# IoT_Sight.net
KiCad netlist of a schematic drawn in EAGLE
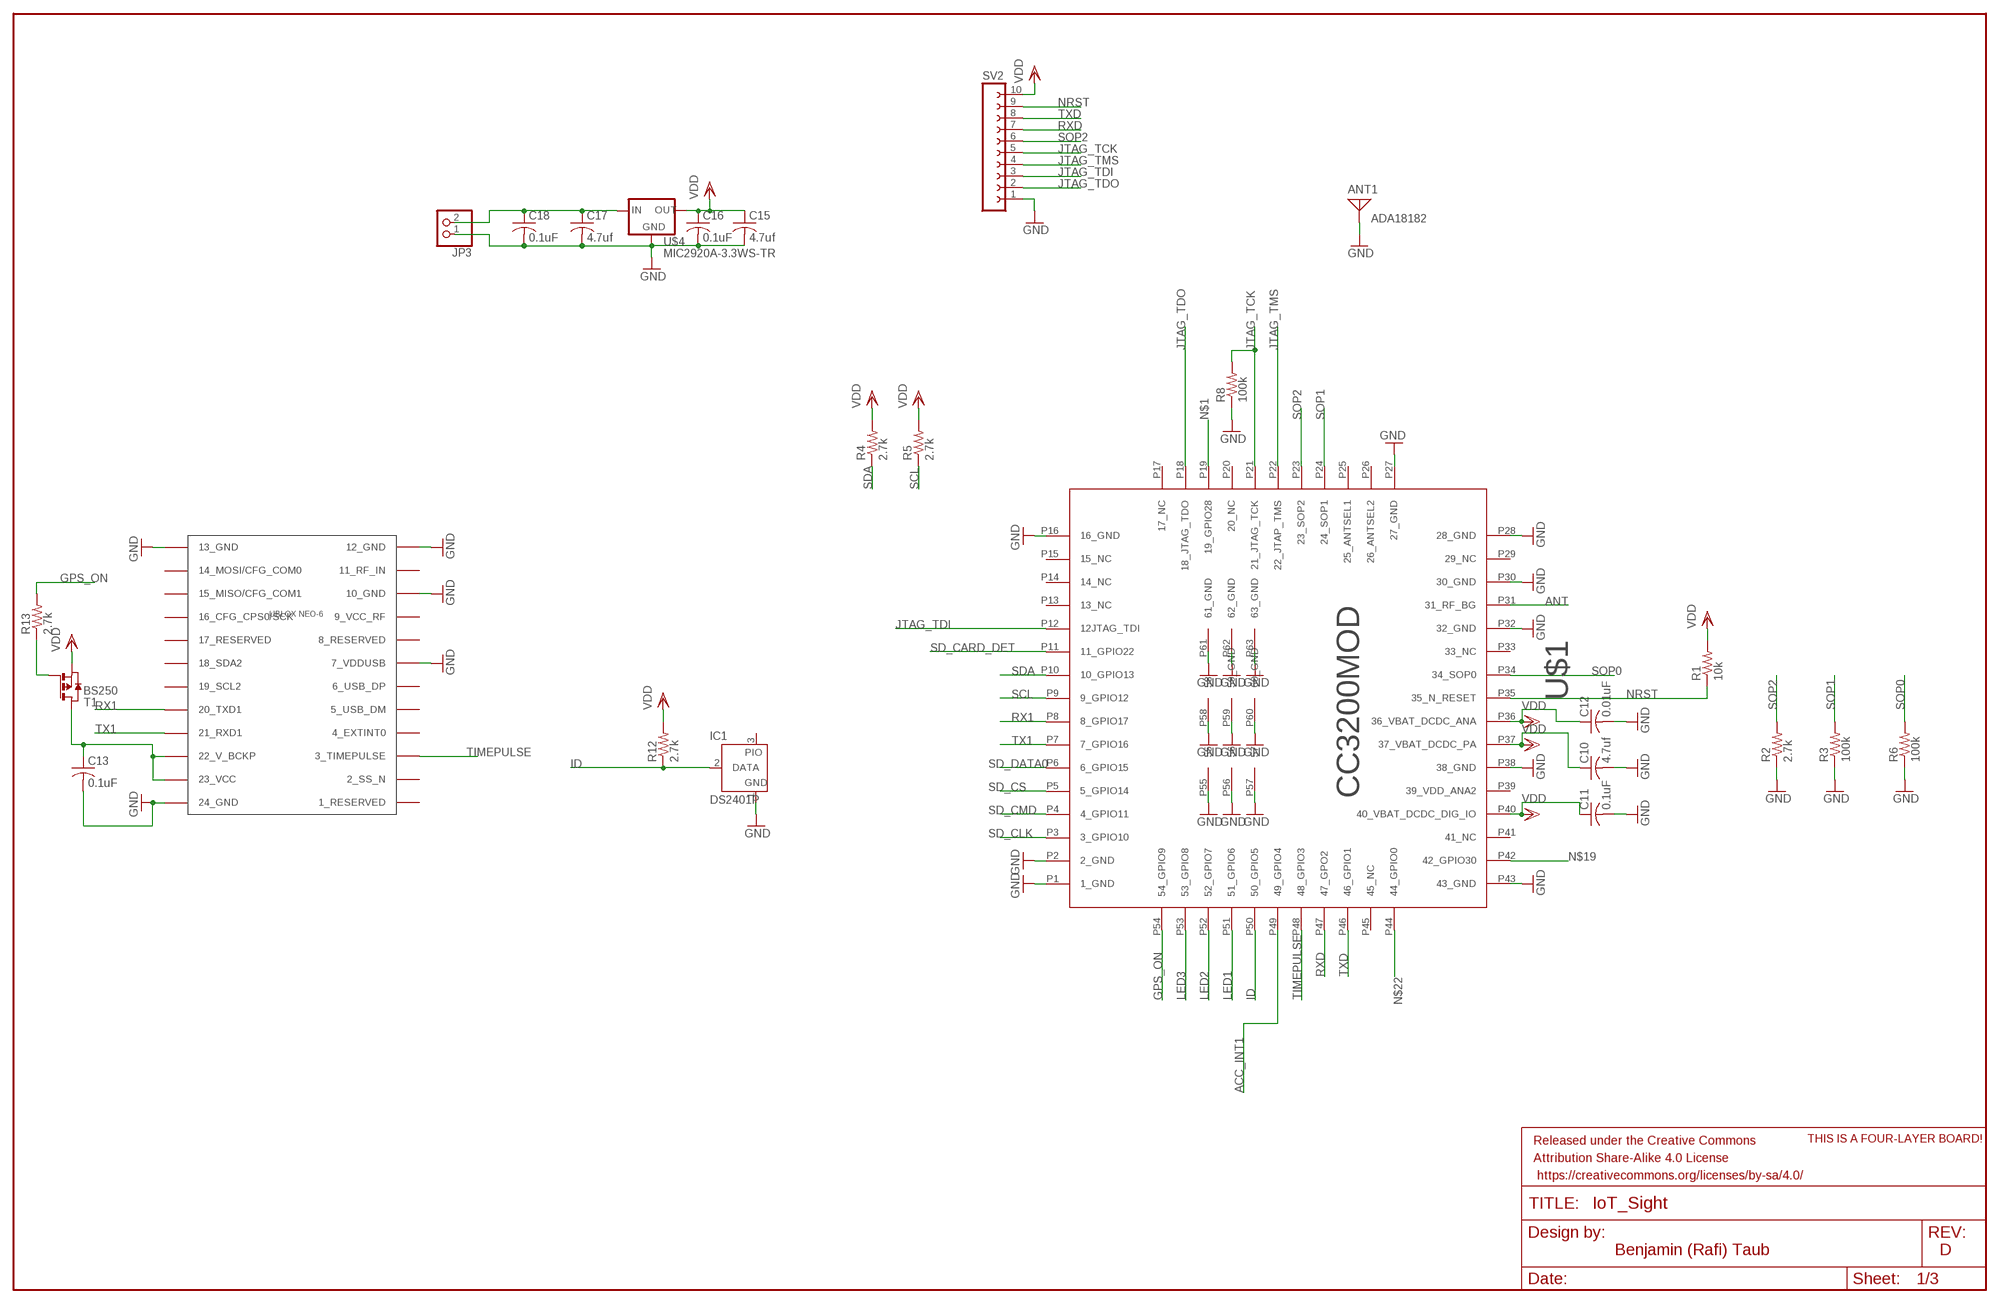
[diagram p0: schematic, sheet 1]
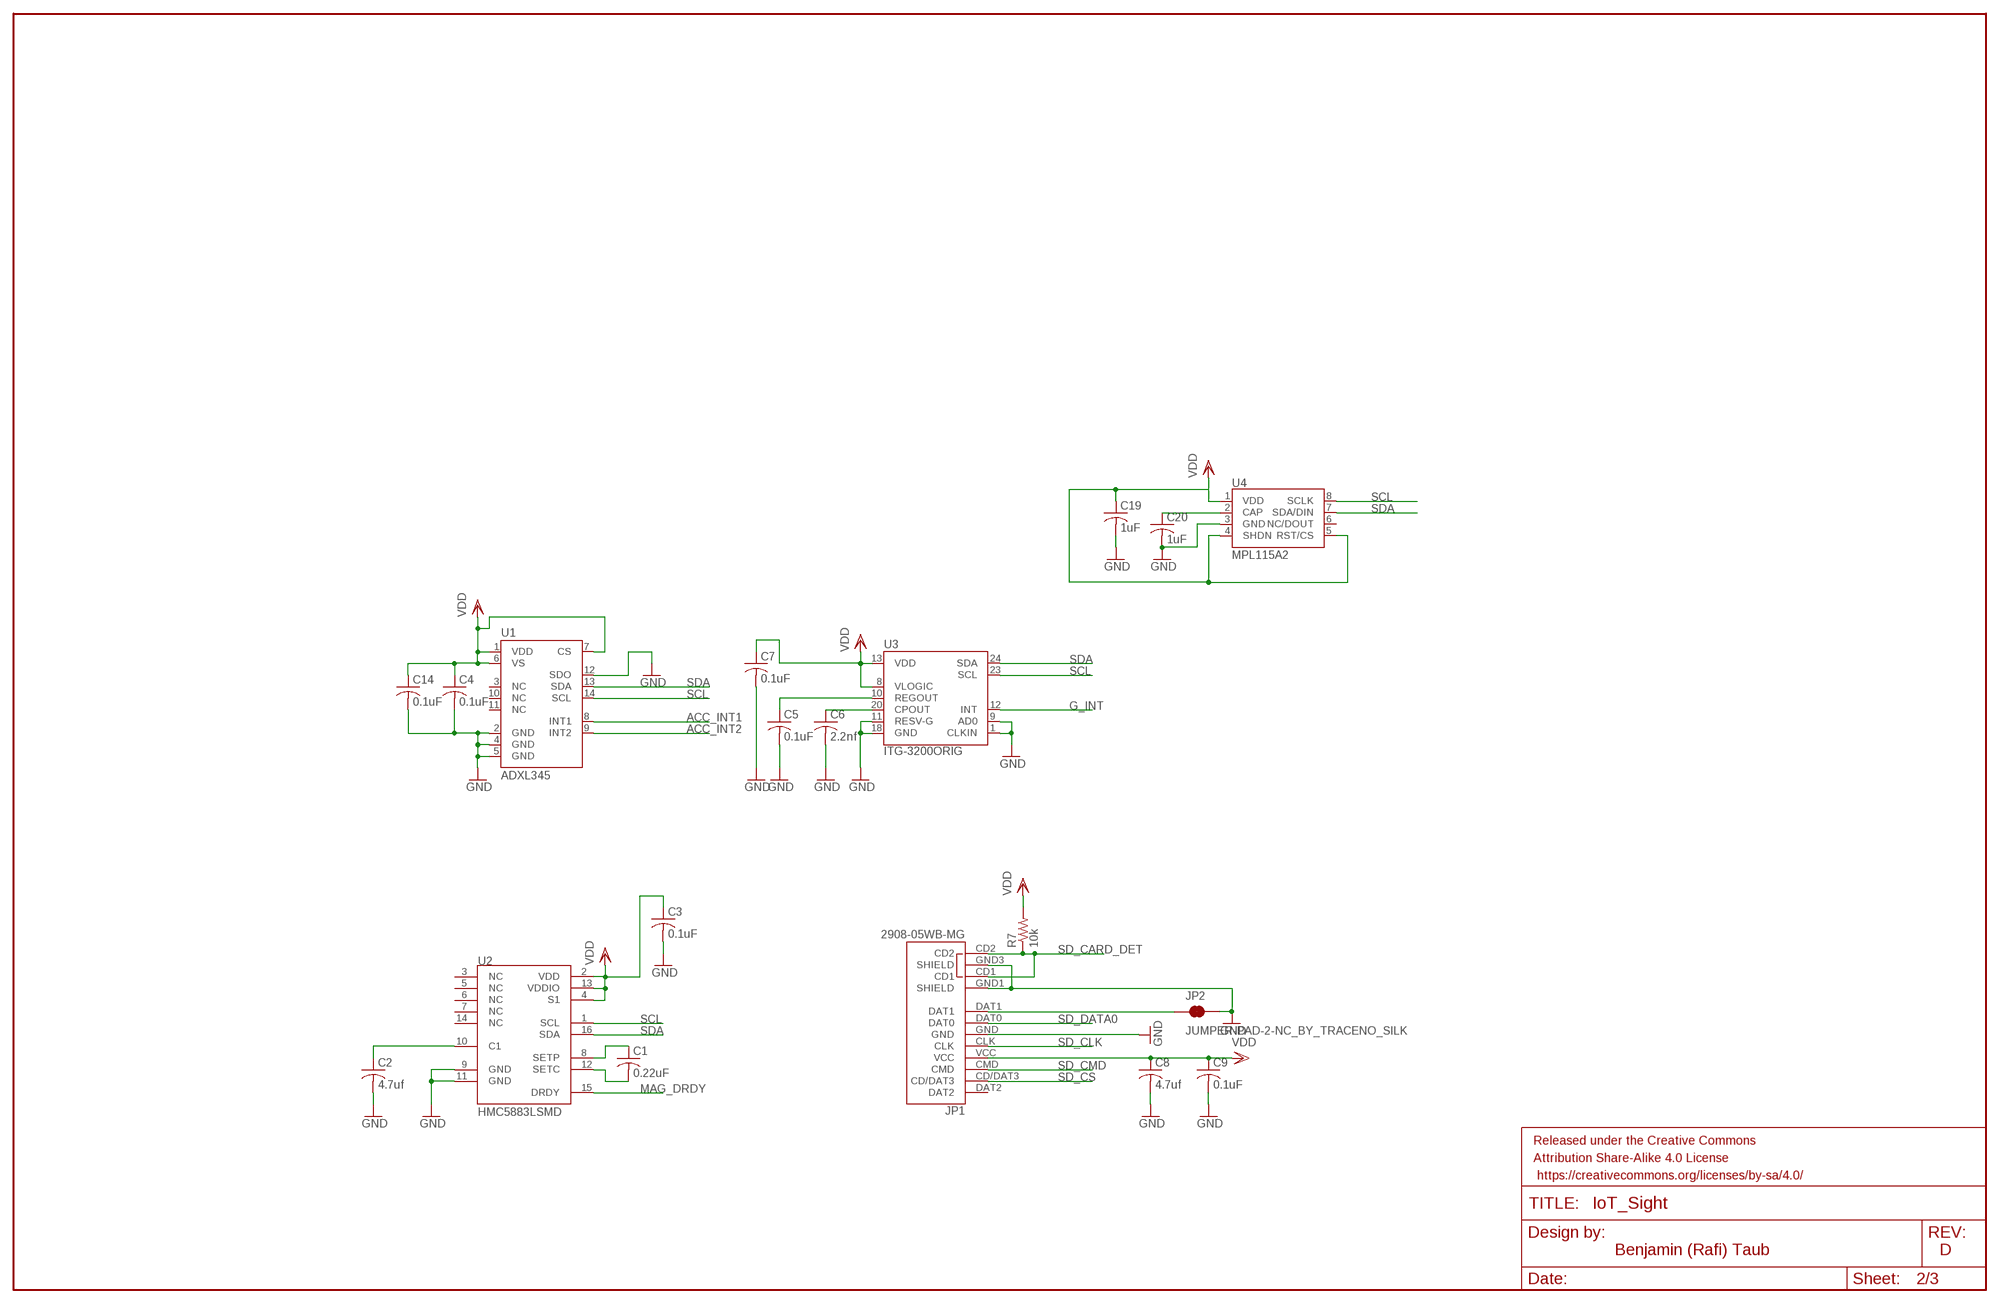
[diagram p1: schematic, sheet 2]
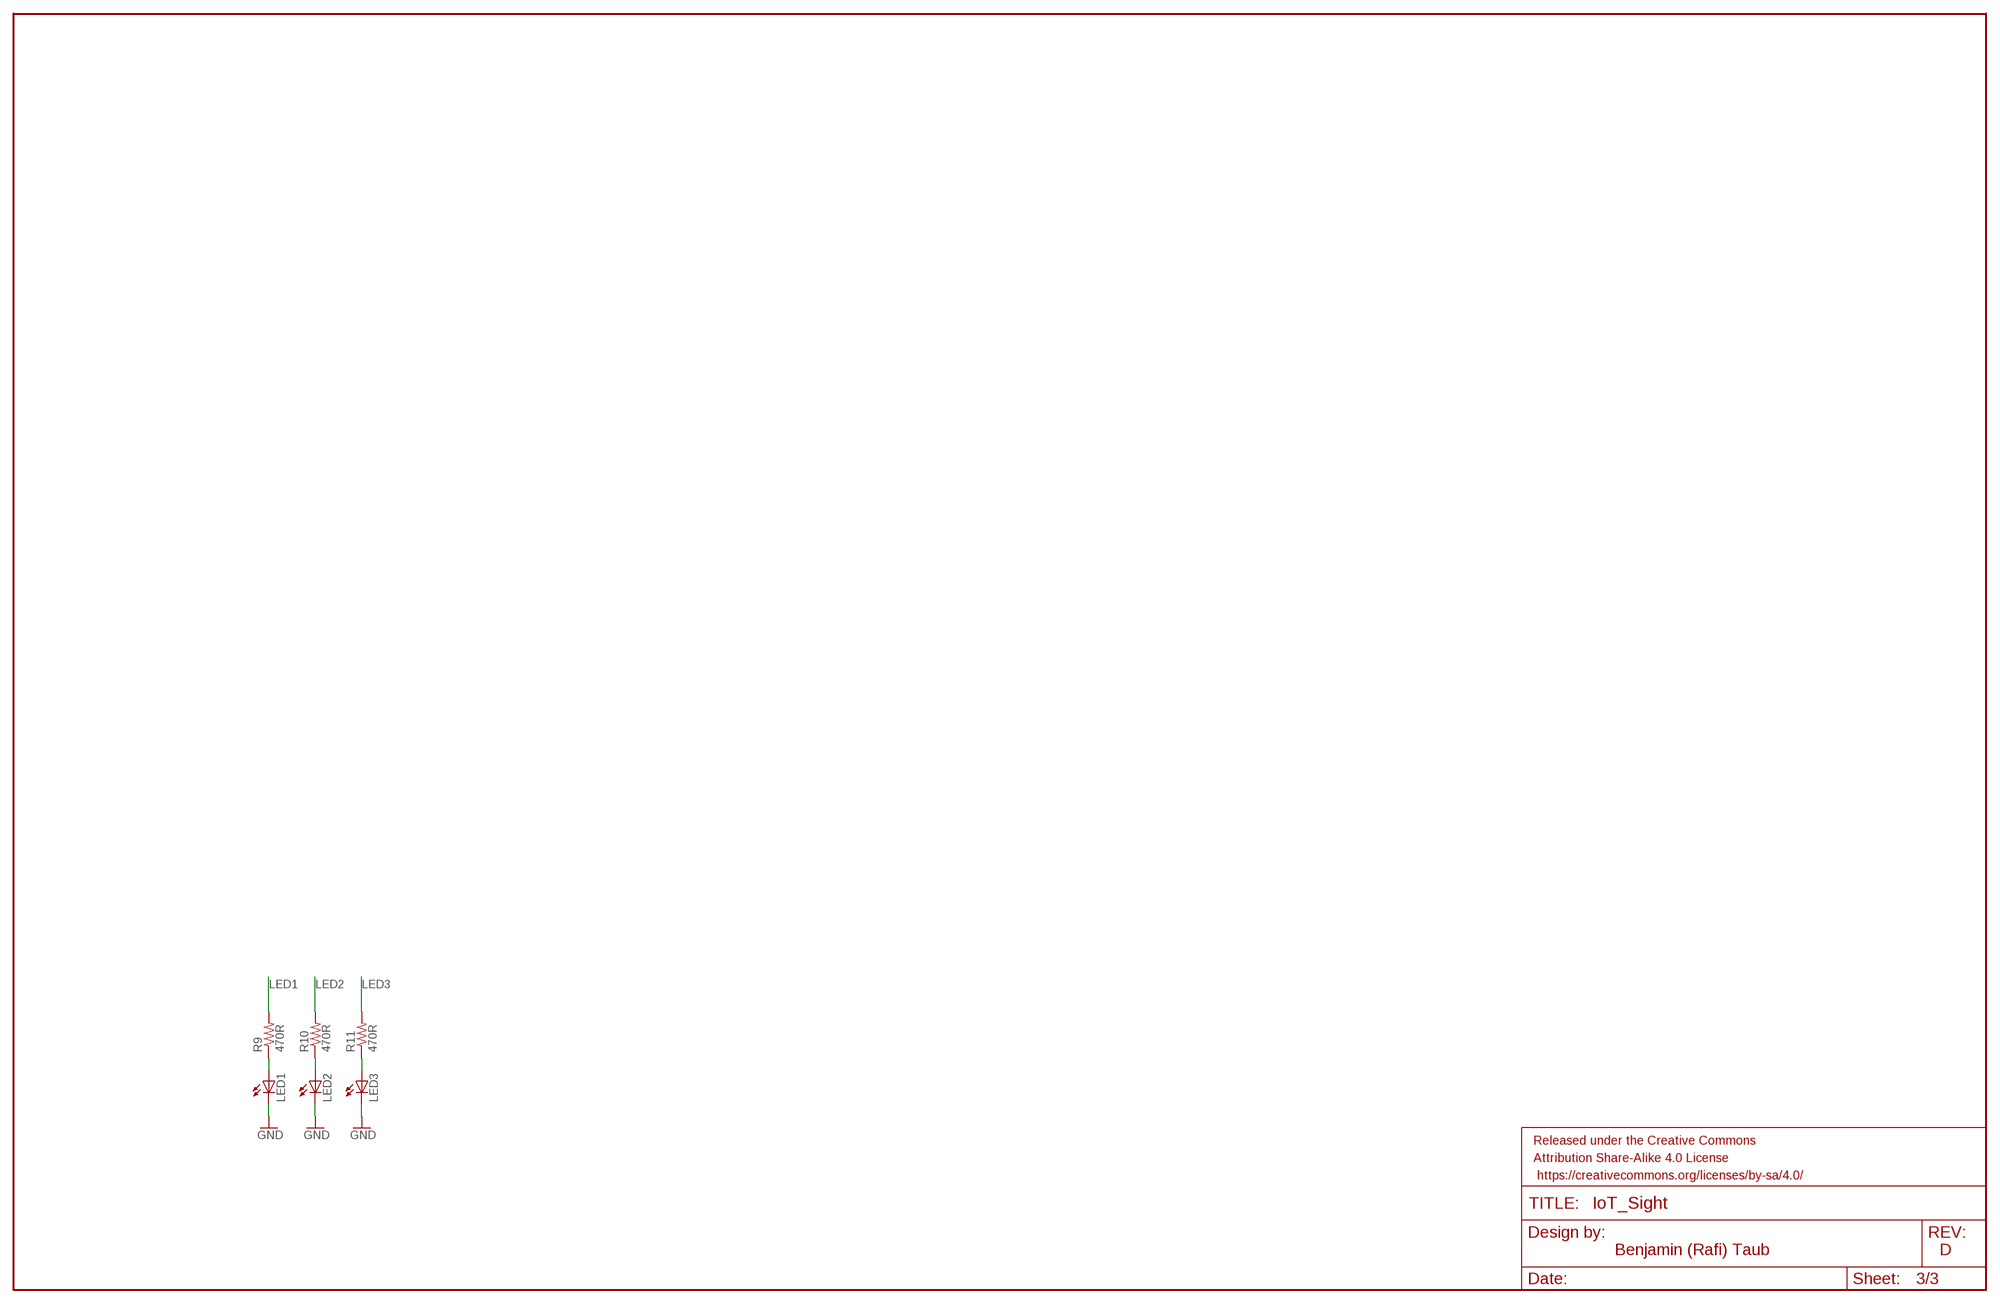
[diagram p2: schematic, sheet 3]

(export (version "E")
  (design (tool "Eeschema 10.0.6"))
  (components
    (comp (ref "FRAME3")
      (value "FRAME-LEDGER")
      (footprint "eagle-import:CREATIVE_COMMONS")
      (libsource (lib "eagle-import") (part "FRAME-LEDGER"))
    )
    (comp (ref "LED1")
      (value "LEDCHIPLED_0805")
      (footprint "eagle-import:CHIPLED_0805")
      (libsource (lib "eagle-import") (part "LEDCHIPLED_0805"))
    )
    (comp (ref "LED2")
      (value "LEDCHIPLED_0805")
      (footprint "eagle-import:CHIPLED_0805")
      (libsource (lib "eagle-import") (part "LEDCHIPLED_0805"))
    )
    (comp (ref "LED3")
      (value "LEDCHIPLED_0805")
      (footprint "eagle-import:CHIPLED_0805")
      (libsource (lib "eagle-import") (part "LEDCHIPLED_0805"))
    )
    (comp (ref "R9")
      (value "470R")
      (footprint "eagle-import:R0603")
      (libsource (lib "eagle-import") (part "R-US_R0603"))
    )
    (comp (ref "R10")
      (value "470R")
      (footprint "eagle-import:R0603")
      (libsource (lib "eagle-import") (part "R-US_R0603"))
    )
    (comp (ref "R11")
      (value "470R")
      (footprint "eagle-import:R0603")
      (libsource (lib "eagle-import") (part "R-US_R0603"))
    )
    (comp (ref "C1")
      (value "0.22uF")
      (footprint "eagle-import:C0805K")
      (libsource (lib "eagle-import") (part "C-USC0805K"))
    )
    (comp (ref "C2")
      (value "4.7uf")
      (footprint "eagle-import:C0805K")
      (libsource (lib "eagle-import") (part "C-USC0805K"))
    )
    (comp (ref "C3")
      (value "0.1uF")
      (footprint "eagle-import:C0805K")
      (libsource (lib "eagle-import") (part "C-USC0805K"))
    )
    (comp (ref "C4")
      (value "0.1uF")
      (footprint "eagle-import:C0805K")
      (libsource (lib "eagle-import") (part "C-USC0805K"))
    )
    (comp (ref "C5")
      (value "0.1uF")
      (footprint "eagle-import:C0805K")
      (libsource (lib "eagle-import") (part "C-USC0805K"))
    )
    (comp (ref "C6")
      (value "2.2nf")
      (footprint "eagle-import:C0805K")
      (libsource (lib "eagle-import") (part "C-USC0805K"))
    )
    (comp (ref "C7")
      (value "0.1uF")
      (footprint "eagle-import:C0805K")
      (libsource (lib "eagle-import") (part "C-USC0805K"))
    )
    (comp (ref "C8")
      (value "4.7uf")
      (footprint "eagle-import:C0805K")
      (libsource (lib "eagle-import") (part "C-USC0805K"))
    )
    (comp (ref "C9")
      (value "0.1uF")
      (footprint "eagle-import:C0805K")
      (libsource (lib "eagle-import") (part "C-USC0805K"))
    )
    (comp (ref "C14")
      (value "0.1uF")
      (footprint "eagle-import:C0805K")
      (libsource (lib "eagle-import") (part "C-USC0805K"))
    )
    (comp (ref "C19")
      (value "1uF")
      (footprint "eagle-import:C0805K")
      (libsource (lib "eagle-import") (part "C-USC0805K"))
    )
    (comp (ref "C20")
      (value "1uF")
      (footprint "eagle-import:C0805K")
      (libsource (lib "eagle-import") (part "C-USC0805K"))
    )
    (comp (ref "FRAME2")
      (value "FRAME-LEDGER")
      (footprint "eagle-import:CREATIVE_COMMONS")
      (libsource (lib "eagle-import") (part "FRAME-LEDGER"))
    )
    (comp (ref "JP1")
      (value "2908-05WB-MG")
      (footprint "eagle-import:MICRO-SD-SOCKET-SDIO")
      (libsource (lib "eagle-import") (part "USD-SDIO-SOCKET"))
    )
    (comp (ref "JP2")
      (value "JUMPER-PAD-2-NC_BY_TRACENO_SILK")
      (footprint "eagle-import:PAD-JUMPER-2-NC_BY_TRACE_NO_SILK")
      (libsource (lib "eagle-import") (part "JUMPER-PAD-2-NC_BY_TRACENO_SILK"))
    )
    (comp (ref "R7")
      (value "10k")
      (footprint "eagle-import:R0603")
      (libsource (lib "eagle-import") (part "R-US_R0603"))
    )
    (comp (ref "U1")
      (value "ADXL345")
      (footprint "eagle-import:LGA14")
      (libsource (lib "eagle-import") (part "ADXL345"))
    )
    (comp (ref "U2")
      (value "HMC5883LSMD")
      (footprint "eagle-import:16LPCC")
      (libsource (lib "eagle-import") (part "HMC5883LSMD"))
    )
    (comp (ref "U3")
      (value "ITG-3200ORIG")
      (footprint "eagle-import:QFN-24")
      (libsource (lib "eagle-import") (part "ITG-3200ORIG"))
    )
    (comp (ref "U4")
      (value "MPL115A2")
      (footprint "eagle-import:LGA8")
      (libsource (lib "eagle-import") (part "MPL115A"))
    )
    (comp (ref "ANT1")
      (value "ADA18182")
      (footprint "eagle-import:PAD-01")
      (libsource (lib "eagle-import") (part "ANTENNA"))
    )
    (comp (ref "C10")
      (value "4.7uf")
      (footprint "eagle-import:C0805K")
      (libsource (lib "eagle-import") (part "C-USC0805K"))
    )
    (comp (ref "C11")
      (value "0.1uF")
      (footprint "eagle-import:C0805K")
      (libsource (lib "eagle-import") (part "C-USC0805K"))
    )
    (comp (ref "C12")
      (value "0.01uF")
      (footprint "eagle-import:C0805K")
      (libsource (lib "eagle-import") (part "C-USC0805K"))
    )
    (comp (ref "C13")
      (value "0.1uF")
      (footprint "eagle-import:C0805K")
      (libsource (lib "eagle-import") (part "C-USC0805K"))
    )
    (comp (ref "C15")
      (value "4.7uf")
      (footprint "eagle-import:C0805K")
      (libsource (lib "eagle-import") (part "C-USC0805K"))
    )
    (comp (ref "C16")
      (value "0.1uF")
      (footprint "eagle-import:C0805K")
      (libsource (lib "eagle-import") (part "C-USC0805K"))
    )
    (comp (ref "C17")
      (value "4.7uf")
      (footprint "eagle-import:C0805K")
      (libsource (lib "eagle-import") (part "C-USC0805K"))
    )
    (comp (ref "C18")
      (value "0.1uF")
      (footprint "eagle-import:C0805K")
      (libsource (lib "eagle-import") (part "C-USC0805K"))
    )
    (comp (ref "FRAME1")
      (value "FRAME-LEDGER")
      (footprint "eagle-import:CREATIVE_COMMONS")
      (libsource (lib "eagle-import") (part "FRAME-LEDGER"))
    )
    (comp (ref "IC1")
      (value "DS2401P")
      (footprint "eagle-import:TSOC6")
      (libsource (lib "eagle-import") (part "DS2405P"))
    )
    (comp (ref "JP3")
      (value "PINHD-1X2")
      (footprint "eagle-import:1X02")
      (libsource (lib "eagle-import") (part "PINHD-1X2"))
    )
    (comp (ref "R1")
      (value "10k")
      (footprint "eagle-import:R0603")
      (libsource (lib "eagle-import") (part "R-US_R0603"))
    )
    (comp (ref "R2")
      (value "2.7k")
      (footprint "eagle-import:R0603")
      (libsource (lib "eagle-import") (part "R-US_R0603"))
    )
    (comp (ref "R3")
      (value "100k")
      (footprint "eagle-import:R0603")
      (libsource (lib "eagle-import") (part "R-US_R0603"))
    )
    (comp (ref "R4")
      (value "2.7k")
      (footprint "eagle-import:R0603")
      (libsource (lib "eagle-import") (part "R-US_R0603"))
    )
    (comp (ref "R5")
      (value "2.7k")
      (footprint "eagle-import:R0603")
      (libsource (lib "eagle-import") (part "R-US_R0603"))
    )
    (comp (ref "R6")
      (value "100k")
      (footprint "eagle-import:R0603")
      (libsource (lib "eagle-import") (part "R-US_R0603"))
    )
    (comp (ref "R8")
      (value "100k")
      (footprint "eagle-import:R0603")
      (libsource (lib "eagle-import") (part "R-US_R0603"))
    )
    (comp (ref "R12")
      (value "2.7k")
      (footprint "eagle-import:R0603")
      (libsource (lib "eagle-import") (part "R-US_R0603"))
    )
    (comp (ref "R13")
      (value "2.7k")
      (footprint "eagle-import:R0603")
      (libsource (lib "eagle-import") (part "R-US_R0603"))
    )
    (comp (ref "SV2")
      (value "FE10-1")
      (footprint "eagle-import:FE10")
      (libsource (lib "eagle-import") (part "FE10-1"))
    )
    (comp (ref "T1")
      (value "BS250")
      (footprint "eagle-import:SOT-23")
      (libsource (lib "eagle-import") (part "PMOSSOT23"))
    )
    (comp (ref "U$1")
      (value "CC3200MOD")
      (footprint "eagle-import:CC3200MOD")
      (libsource (lib "eagle-import") (part "CC3200"))
    )
    (comp (ref "U$2")
      (value "UBLOX_NEO-7")
      (footprint "eagle-import:UBLOX_NEO-6P")
      (libsource (lib "eagle-import") (part "UBLOX_NEO-6"))
    )
    (comp (ref "U$3")
      (value "FOUR_LAYER_WARNING")
      (footprint "eagle-import:FOUR_LAYER_WARNING")
      (libsource (lib "eagle-import") (part "FOUR_LAYER_WARNING"))
    )
    (comp (ref "U$4")
      (value "MIC2920A-3.3WS-TR")
      (footprint "eagle-import:SOT223")
      (libsource (lib "eagle-import") (part "V_REG_MIC2920"))
    )
  )
  (nets
    (net (code "1") (name "ACC_INT1") (class "Default")
      (node (ref "U$1") (pin "P49") (pinfunction "49_GPIO4_P49") (pintype "bidirectional"))
      (node (ref "U1") (pin "8") (pinfunction "INT1_8") (pintype "bidirectional"))
    )
    (net (code "2") (name "ACC_INT2") (class "Default")
      (node (ref "U1") (pin "9") (pinfunction "INT2_9") (pintype "bidirectional"))
    )
    (net (code "3") (name "ANT") (class "Default")
      (node (ref "U$1") (pin "P31") (pinfunction "31_RF_BG_P31") (pintype "bidirectional"))
    )
    (net (code "4") (name "GND") (class "Default")
      (node (ref "ANT1") (pin "1") (pinfunction "1_1") (pintype "output"))
      (node (ref "C10") (pin "2") (pinfunction "2_2") (pintype "passive"))
      (node (ref "C11") (pin "2") (pinfunction "2_2") (pintype "passive"))
      (node (ref "C12") (pin "2") (pinfunction "2_2") (pintype "passive"))
      (node (ref "C13") (pin "2") (pinfunction "2_2") (pintype "passive"))
      (node (ref "C14") (pin "2") (pinfunction "2_2") (pintype "passive"))
      (node (ref "C15") (pin "2") (pinfunction "2_2") (pintype "passive"))
      (node (ref "C16") (pin "2") (pinfunction "2_2") (pintype "passive"))
      (node (ref "C17") (pin "2") (pinfunction "2_2") (pintype "passive"))
      (node (ref "C18") (pin "2") (pinfunction "2_2") (pintype "passive"))
      (node (ref "C19") (pin "2") (pinfunction "2_2") (pintype "passive"))
      (node (ref "C2") (pin "2") (pinfunction "2_2") (pintype "passive"))
      (node (ref "C20") (pin "2") (pinfunction "2_2") (pintype "passive"))
      (node (ref "C3") (pin "2") (pinfunction "2_2") (pintype "passive"))
      (node (ref "C4") (pin "2") (pinfunction "2_2") (pintype "passive"))
      (node (ref "C5") (pin "2") (pinfunction "2_2") (pintype "passive"))
      (node (ref "C6") (pin "2") (pinfunction "2_2") (pintype "passive"))
      (node (ref "C7") (pin "2") (pinfunction "2_2") (pintype "passive"))
      (node (ref "C8") (pin "2") (pinfunction "2_2") (pintype "passive"))
      (node (ref "C9") (pin "2") (pinfunction "2_2") (pintype "passive"))
      (node (ref "IC1") (pin "1") (pinfunction "GND_1") (pintype "passive"))
      (node (ref "JP1") (pin "GND") (pinfunction "GND_GND") (pintype "bidirectional"))
      (node (ref "JP1") (pin "GND1") (pinfunction "SHIELD_GND1") (pintype "bidirectional"))
      (node (ref "JP1") (pin "GND3") (pinfunction "SHIELD_GND3") (pintype "bidirectional"))
      (node (ref "JP2") (pin "2") (pinfunction "2_2") (pintype "passive"))
      (node (ref "JP3") (pin "1") (pinfunction "1_1") (pintype "passive"))
      (node (ref "LED1") (pin "C") (pinfunction "C_C") (pintype "passive"))
      (node (ref "LED2") (pin "C") (pinfunction "C_C") (pintype "passive"))
      (node (ref "LED3") (pin "C") (pinfunction "C_C") (pintype "passive"))
      (node (ref "R2") (pin "1") (pinfunction "1_1") (pintype "passive"))
      (node (ref "R3") (pin "1") (pinfunction "1_1") (pintype "passive"))
      (node (ref "R6") (pin "1") (pinfunction "1_1") (pintype "passive"))
      (node (ref "R8") (pin "1") (pinfunction "1_1") (pintype "passive"))
      (node (ref "SV2") (pin "1") (pinfunction "1_1") (pintype "passive"))
      (node (ref "U$1") (pin "P1") (pinfunction "1_GND_P1") (pintype "bidirectional"))
      (node (ref "U$1") (pin "P16") (pinfunction "16_GND_P16") (pintype "bidirectional"))
      (node (ref "U$1") (pin "P2") (pinfunction "2_GND_P2") (pintype "bidirectional"))
      (node (ref "U$1") (pin "P27") (pinfunction "27_GND_P27") (pintype "bidirectional"))
      (node (ref "U$1") (pin "P28") (pinfunction "28_GND_P28") (pintype "bidirectional"))
      (node (ref "U$1") (pin "P30") (pinfunction "30_GND_P30") (pintype "bidirectional"))
      (node (ref "U$1") (pin "P32") (pinfunction "32_GND_P32") (pintype "bidirectional"))
      (node (ref "U$1") (pin "P38") (pinfunction "38_GND_P38") (pintype "bidirectional"))
      (node (ref "U$1") (pin "P43") (pinfunction "43_GND_P43") (pintype "bidirectional"))
      (node (ref "U$1") (pin "P55") (pinfunction "55_P55") (pintype "bidirectional"))
      (node (ref "U$1") (pin "P56") (pinfunction "56_P56") (pintype "bidirectional"))
      (node (ref "U$1") (pin "P57") (pinfunction "57_P57") (pintype "bidirectional"))
      (node (ref "U$1") (pin "P58") (pinfunction "58_P58") (pintype "bidirectional"))
      (node (ref "U$1") (pin "P59") (pinfunction "59_GND_P59") (pintype "bidirectional"))
      (node (ref "U$1") (pin "P60") (pinfunction "60_GND_P60") (pintype "bidirectional"))
      (node (ref "U$1") (pin "P61") (pinfunction "61_GND_P61") (pintype "bidirectional"))
      (node (ref "U$1") (pin "P62") (pinfunction "62_GND_P62") (pintype "bidirectional"))
      (node (ref "U$1") (pin "P63") (pinfunction "63_GND_P63") (pintype "bidirectional"))
      (node (ref "U$2") (pin "10_GND") (pinfunction "10_GND_10_GND") (pintype "bidirectional"))
      (node (ref "U$2") (pin "12_GND") (pinfunction "12_GND_12_GND") (pintype "bidirectional"))
      (node (ref "U$2") (pin "13_GND") (pinfunction "13_GND_13_GND") (pintype "bidirectional"))
      (node (ref "U$2") (pin "24_GND") (pinfunction "24_GND_24_GND") (pintype "bidirectional"))
      (node (ref "U$2") (pin "7_VDDUSB") (pinfunction "7_VDDUSB_7_VDDUSB") (pintype "bidirectional"))
      (node (ref "U$4") (pin "2") (pinfunction "GND_2") (pintype "input"))
      (node (ref "U1") (pin "12") (pinfunction "SDO_12") (pintype "bidirectional"))
      (node (ref "U1") (pin "2") (pinfunction "GND_2") (pintype "bidirectional"))
      (node (ref "U1") (pin "4") (pinfunction "GND_4") (pintype "bidirectional"))
      (node (ref "U1") (pin "5") (pinfunction "GND_5") (pintype "bidirectional"))
      (node (ref "U2") (pin "11") (pinfunction "GND_11") (pintype "bidirectional"))
      (node (ref "U2") (pin "9") (pinfunction "GND_9") (pintype "bidirectional"))
      (node (ref "U3") (pin "1") (pinfunction "CLKIN_1") (pintype "bidirectional"))
      (node (ref "U3") (pin "11") (pinfunction "RESV-G_11") (pintype "bidirectional"))
      (node (ref "U3") (pin "18") (pinfunction "GND_18") (pintype "bidirectional"))
      (node (ref "U3") (pin "9") (pinfunction "AD0_9") (pintype "bidirectional"))
      (node (ref "U4") (pin "3") (pinfunction "GND_3") (pintype "bidirectional"))
    )
    (net (code "5") (name "GPS_ON") (class "Default")
      (node (ref "R13") (pin "2") (pinfunction "2_2") (pintype "passive"))
      (node (ref "U$1") (pin "P54") (pinfunction "54_GPIO9_P54") (pintype "bidirectional"))
    )
    (net (code "6") (name "G_INT") (class "Default")
      (node (ref "U3") (pin "12") (pinfunction "INT_12") (pintype "bidirectional"))
    )
    (net (code "7") (name "ID") (class "Default")
      (node (ref "IC1") (pin "2") (pinfunction "DATA_2") (pintype "input"))
      (node (ref "R12") (pin "1") (pinfunction "1_1") (pintype "passive"))
      (node (ref "U$1") (pin "P50") (pinfunction "50_GPIO5_P50") (pintype "bidirectional"))
    )
    (net (code "8") (name "JTAG_TCK") (class "Default")
      (node (ref "R8") (pin "2") (pinfunction "2_2") (pintype "passive"))
      (node (ref "SV2") (pin "5") (pinfunction "5_5") (pintype "passive"))
      (node (ref "U$1") (pin "P21") (pinfunction "21_JTAG_TCK_P21") (pintype "bidirectional"))
    )
    (net (code "9") (name "JTAG_TDI") (class "Default")
      (node (ref "SV2") (pin "3") (pinfunction "3_3") (pintype "passive"))
      (node (ref "U$1") (pin "P12") (pinfunction "12JTAG_TDI_P12") (pintype "bidirectional"))
    )
    (net (code "10") (name "JTAG_TDO") (class "Default")
      (node (ref "SV2") (pin "2") (pinfunction "2_2") (pintype "passive"))
      (node (ref "U$1") (pin "P18") (pinfunction "18_JTAG_TDO_P18") (pintype "bidirectional"))
    )
    (net (code "11") (name "JTAG_TMS") (class "Default")
      (node (ref "SV2") (pin "4") (pinfunction "4_4") (pintype "passive"))
      (node (ref "U$1") (pin "P22") (pinfunction "22_JTAP_TMS_P22") (pintype "bidirectional"))
    )
    (net (code "12") (name "LED1") (class "Default")
      (node (ref "R9") (pin "2") (pinfunction "2_2") (pintype "passive"))
      (node (ref "U$1") (pin "P51") (pinfunction "51_GPIO6_P51") (pintype "bidirectional"))
    )
    (net (code "13") (name "LED2") (class "Default")
      (node (ref "R10") (pin "2") (pinfunction "2_2") (pintype "passive"))
      (node (ref "U$1") (pin "P52") (pinfunction "52_GPIO7_P52") (pintype "bidirectional"))
    )
    (net (code "14") (name "LED3") (class "Default")
      (node (ref "R11") (pin "2") (pinfunction "2_2") (pintype "passive"))
      (node (ref "U$1") (pin "P53") (pinfunction "53_GPIO8_P53") (pintype "bidirectional"))
    )
    (net (code "15") (name "MAG_DRDY") (class "Default")
      (node (ref "U2") (pin "15") (pinfunction "DRDY_15") (pintype "bidirectional"))
    )
    (net (code "16") (name "N$1") (class "Default")
      (node (ref "U$1") (pin "P19") (pinfunction "19_GPIO28_P19") (pintype "bidirectional"))
    )
    (net (code "17") (name "N$19") (class "Default")
      (node (ref "U$1") (pin "P42") (pinfunction "42_GPIO30_P42") (pintype "bidirectional"))
    )
    (net (code "18") (name "N$22") (class "Default")
      (node (ref "U$1") (pin "P44") (pinfunction "44_GPIO0_P44") (pintype "bidirectional"))
    )
    (net (code "19") (name "NRST") (class "Default")
      (node (ref "R1") (pin "1") (pinfunction "1_1") (pintype "passive"))
      (node (ref "SV2") (pin "9") (pinfunction "9_9") (pintype "passive"))
      (node (ref "U$1") (pin "P35") (pinfunction "35_N_RESET_P35") (pintype "bidirectional"))
    )
    (net (code "20") (name "Net-(JP1-PadDAT1)") (class "Default")
      (node (ref "JP1") (pin "DAT1") (pinfunction "DAT1_DAT1") (pintype "bidirectional"))
      (node (ref "JP2") (pin "1") (pinfunction "1_1") (pintype "passive"))
    )
    (net (code "21") (name "Net-(LED1-PadA)") (class "Default")
      (node (ref "LED1") (pin "A") (pinfunction "A_A") (pintype "passive"))
      (node (ref "R9") (pin "1") (pinfunction "1_1") (pintype "passive"))
    )
    (net (code "22") (name "Net-(LED2-PadA)") (class "Default")
      (node (ref "LED2") (pin "A") (pinfunction "A_A") (pintype "passive"))
      (node (ref "R10") (pin "1") (pinfunction "1_1") (pintype "passive"))
    )
    (net (code "23") (name "Net-(LED3-PadA)") (class "Default")
      (node (ref "LED3") (pin "A") (pinfunction "A_A") (pintype "passive"))
      (node (ref "R11") (pin "1") (pinfunction "1_1") (pintype "passive"))
    )
    (net (code "24") (name "Net-(T1-D)") (class "Default")
      (node (ref "C13") (pin "1") (pinfunction "1_1") (pintype "passive"))
      (node (ref "T1") (pin "1") (pinfunction "D_1") (pintype "passive"))
      (node (ref "U$2") (pin "22_V_BCKP") (pinfunction "22_V_BCKP_22_V_BCKP") (pintype "bidirectional"))
      (node (ref "U$2") (pin "23_VCC") (pinfunction "23_VCC_23_VCC") (pintype "bidirectional"))
    )
    (net (code "25") (name "Net-(T1-G)") (class "Default")
      (node (ref "R13") (pin "1") (pinfunction "1_1") (pintype "passive"))
      (node (ref "T1") (pin "3") (pinfunction "G_3") (pintype "passive"))
    )
    (net (code "26") (name "Net-(U$4-IN)") (class "Default")
      (node (ref "C17") (pin "1") (pinfunction "1_1") (pintype "passive"))
      (node (ref "C18") (pin "1") (pinfunction "1_1") (pintype "passive"))
      (node (ref "JP3") (pin "2") (pinfunction "2_2") (pintype "passive"))
      (node (ref "U$4") (pin "1") (pinfunction "IN_1") (pintype "input"))
    )
    (net (code "27") (name "Net-(U2-C1)") (class "Default")
      (node (ref "C2") (pin "1") (pinfunction "1_1") (pintype "passive"))
      (node (ref "U2") (pin "10") (pinfunction "C1_10") (pintype "bidirectional"))
    )
    (net (code "28") (name "Net-(U2-SETC)") (class "Default")
      (node (ref "C1") (pin "2") (pinfunction "2_2") (pintype "passive"))
      (node (ref "U2") (pin "12") (pinfunction "SETC_12") (pintype "bidirectional"))
    )
    (net (code "29") (name "Net-(U2-SETP)") (class "Default")
      (node (ref "C1") (pin "1") (pinfunction "1_1") (pintype "passive"))
      (node (ref "U2") (pin "8") (pinfunction "SETP_8") (pintype "bidirectional"))
    )
    (net (code "30") (name "Net-(U3-CPOUT)") (class "Default")
      (node (ref "C6") (pin "1") (pinfunction "1_1") (pintype "passive"))
      (node (ref "U3") (pin "20") (pinfunction "CPOUT_20") (pintype "bidirectional"))
    )
    (net (code "31") (name "Net-(U3-REGOUT)") (class "Default")
      (node (ref "C5") (pin "1") (pinfunction "1_1") (pintype "passive"))
      (node (ref "U3") (pin "10") (pinfunction "REGOUT_10") (pintype "bidirectional"))
    )
    (net (code "32") (name "Net-(U4-CAP)") (class "Default")
      (node (ref "C20") (pin "1") (pinfunction "1_1") (pintype "passive"))
      (node (ref "U4") (pin "2") (pinfunction "CAP_2") (pintype "bidirectional"))
    )
    (net (code "33") (name "RX1") (class "Default")
      (node (ref "U$1") (pin "P8") (pinfunction "8_GPIO17_P8") (pintype "bidirectional"))
      (node (ref "U$2") (pin "20_TXD1") (pinfunction "20_TXD1_20_TXD1") (pintype "bidirectional"))
    )
    (net (code "34") (name "RXD") (class "Default")
      (node (ref "SV2") (pin "7") (pinfunction "7_7") (pintype "passive"))
      (node (ref "U$1") (pin "P47") (pinfunction "47_GPO2_P47") (pintype "bidirectional"))
    )
    (net (code "35") (name "SCL") (class "Default")
      (node (ref "R5") (pin "1") (pinfunction "1_1") (pintype "passive"))
      (node (ref "U$1") (pin "P9") (pinfunction "9_GPIO12_P9") (pintype "bidirectional"))
      (node (ref "U1") (pin "14") (pinfunction "SCL_14") (pintype "bidirectional"))
      (node (ref "U2") (pin "1") (pinfunction "SCL_1") (pintype "bidirectional"))
      (node (ref "U3") (pin "23") (pinfunction "SCL_23") (pintype "bidirectional"))
      (node (ref "U4") (pin "8") (pinfunction "SCLK_8") (pintype "bidirectional"))
    )
    (net (code "36") (name "SDA") (class "Default")
      (node (ref "R4") (pin "1") (pinfunction "1_1") (pintype "passive"))
      (node (ref "U$1") (pin "P10") (pinfunction "10_GPIO13_P10") (pintype "bidirectional"))
      (node (ref "U1") (pin "13") (pinfunction "SDA_13") (pintype "bidirectional"))
      (node (ref "U2") (pin "16") (pinfunction "SDA_16") (pintype "bidirectional"))
      (node (ref "U3") (pin "24") (pinfunction "SDA_24") (pintype "bidirectional"))
      (node (ref "U4") (pin "7") (pinfunction "SDA/DIN_7") (pintype "bidirectional"))
    )
    (net (code "37") (name "SD_CARD_DET") (class "Default")
      (node (ref "JP1") (pin "CD1") (pinfunction "CD1_CD1") (pintype "bidirectional"))
      (node (ref "JP1") (pin "CD2") (pinfunction "CD2_CD2") (pintype "bidirectional"))
      (node (ref "R7") (pin "1") (pinfunction "1_1") (pintype "passive"))
      (node (ref "U$1") (pin "P11") (pinfunction "11_GPIO22_P11") (pintype "bidirectional"))
    )
    (net (code "38") (name "SD_CLK") (class "Default")
      (node (ref "JP1") (pin "CLK") (pinfunction "CLK_CLK") (pintype "bidirectional"))
      (node (ref "U$1") (pin "P3") (pinfunction "3_GPIO10_P3") (pintype "bidirectional"))
    )
    (net (code "39") (name "SD_CMD") (class "Default")
      (node (ref "JP1") (pin "CMD") (pinfunction "CMD_CMD") (pintype "bidirectional"))
      (node (ref "U$1") (pin "P4") (pinfunction "4_GPIO11_P4") (pintype "bidirectional"))
    )
    (net (code "40") (name "SD_CS") (class "Default")
      (node (ref "JP1") (pin "CD/DAT3") (pinfunction "CD/DAT3_CD/DAT3") (pintype "bidirectional"))
      (node (ref "U$1") (pin "P5") (pinfunction "5_GPIO14_P5") (pintype "bidirectional"))
    )
    (net (code "41") (name "SD_DATA0") (class "Default")
      (node (ref "JP1") (pin "DAT0") (pinfunction "DAT0_DAT0") (pintype "bidirectional"))
      (node (ref "U$1") (pin "P6") (pinfunction "6_GPIO15_P6") (pintype "bidirectional"))
    )
    (net (code "42") (name "SOP0") (class "Default")
      (node (ref "R6") (pin "2") (pinfunction "2_2") (pintype "passive"))
      (node (ref "U$1") (pin "P34") (pinfunction "34_SOP0_P34") (pintype "bidirectional"))
    )
    (net (code "43") (name "SOP1") (class "Default")
      (node (ref "R3") (pin "2") (pinfunction "2_2") (pintype "passive"))
      (node (ref "U$1") (pin "P24") (pinfunction "24_SOP1_P24") (pintype "bidirectional"))
    )
    (net (code "44") (name "SOP2") (class "Default")
      (node (ref "R2") (pin "2") (pinfunction "2_2") (pintype "passive"))
      (node (ref "SV2") (pin "6") (pinfunction "6_6") (pintype "passive"))
      (node (ref "U$1") (pin "P23") (pinfunction "23_SOP2_P23") (pintype "bidirectional"))
    )
    (net (code "45") (name "TIMEPULSE") (class "Default")
      (node (ref "U$1") (pin "P48") (pinfunction "48_GPIO3_P48") (pintype "bidirectional"))
      (node (ref "U$2") (pin "3_TIMEPULSE") (pinfunction "3_TIMEPULSE_3_TIMEPULSE") (pintype "bidirectional"))
    )
    (net (code "46") (name "TX1") (class "Default")
      (node (ref "U$1") (pin "P7") (pinfunction "7_GPIO16_P7") (pintype "bidirectional"))
      (node (ref "U$2") (pin "21_RXD1") (pinfunction "21_RXD1_21_RXD1") (pintype "bidirectional"))
    )
    (net (code "47") (name "TXD") (class "Default")
      (node (ref "SV2") (pin "8") (pinfunction "8_8") (pintype "passive"))
      (node (ref "U$1") (pin "P46") (pinfunction "46_GPIO1_P46") (pintype "bidirectional"))
    )
    (net (code "48") (name "VDD") (class "Default")
      (node (ref "C10") (pin "1") (pinfunction "1_1") (pintype "passive"))
      (node (ref "C11") (pin "1") (pinfunction "1_1") (pintype "passive"))
      (node (ref "C12") (pin "1") (pinfunction "1_1") (pintype "passive"))
      (node (ref "C14") (pin "1") (pinfunction "1_1") (pintype "passive"))
      (node (ref "C15") (pin "1") (pinfunction "1_1") (pintype "passive"))
      (node (ref "C16") (pin "1") (pinfunction "1_1") (pintype "passive"))
      (node (ref "C19") (pin "1") (pinfunction "1_1") (pintype "passive"))
      (node (ref "C3") (pin "1") (pinfunction "1_1") (pintype "passive"))
      (node (ref "C4") (pin "1") (pinfunction "1_1") (pintype "passive"))
      (node (ref "C7") (pin "1") (pinfunction "1_1") (pintype "passive"))
      (node (ref "C8") (pin "1") (pinfunction "1_1") (pintype "passive"))
      (node (ref "C9") (pin "1") (pinfunction "1_1") (pintype "passive"))
      (node (ref "JP1") (pin "VCC") (pinfunction "VCC_VCC") (pintype "bidirectional"))
      (node (ref "R1") (pin "2") (pinfunction "2_2") (pintype "passive"))
      (node (ref "R12") (pin "2") (pinfunction "2_2") (pintype "passive"))
      (node (ref "R4") (pin "2") (pinfunction "2_2") (pintype "passive"))
      (node (ref "R5") (pin "2") (pinfunction "2_2") (pintype "passive"))
      (node (ref "R7") (pin "2") (pinfunction "2_2") (pintype "passive"))
      (node (ref "SV2") (pin "10") (pinfunction "10_10") (pintype "passive"))
      (node (ref "T1") (pin "2") (pinfunction "S_2") (pintype "passive"))
      (node (ref "U$1") (pin "P36") (pinfunction "36_VBAT_DCDC_ANA_P36") (pintype "bidirectional"))
      (node (ref "U$1") (pin "P37") (pinfunction "37_VBAT_DCDC_PA_P37") (pintype "bidirectional"))
      (node (ref "U$1") (pin "P40") (pinfunction "40_VBAT_DCDC_DIG_IO_P40") (pintype "bidirectional"))
      (node (ref "U$4") (pin "3") (pinfunction "OUT_3") (pintype "passive"))
      (node (ref "U1") (pin "1") (pinfunction "VDD_1") (pintype "bidirectional"))
      (node (ref "U1") (pin "6") (pinfunction "VS_6") (pintype "bidirectional"))
      (node (ref "U1") (pin "7") (pinfunction "CS_7") (pintype "bidirectional"))
      (node (ref "U2") (pin "13") (pinfunction "VDDIO_13") (pintype "bidirectional"))
      (node (ref "U2") (pin "2") (pinfunction "VDD_2") (pintype "bidirectional"))
      (node (ref "U2") (pin "4") (pinfunction "S1_4") (pintype "bidirectional"))
      (node (ref "U3") (pin "13") (pinfunction "VDD_13") (pintype "bidirectional"))
      (node (ref "U3") (pin "8") (pinfunction "VLOGIC_8") (pintype "bidirectional"))
      (node (ref "U4") (pin "1") (pinfunction "VDD_1") (pintype "bidirectional"))
      (node (ref "U4") (pin "4") (pinfunction "SHDN_4") (pintype "bidirectional"))
      (node (ref "U4") (pin "5") (pinfunction "RST/CS_5") (pintype "bidirectional"))
    )
    (net (code "49") (name "unconnected-(IC1-PIO-Pad3)") (class "Default")
      (node (ref "IC1") (pin "3") (pinfunction "PIO_3") (pintype "passive"))
    )
    (net (code "50") (name "unconnected-(JP1-PadDAT2)") (class "Default")
      (node (ref "JP1") (pin "DAT2") (pinfunction "DAT2_DAT2") (pintype "bidirectional"))
    )
    (net (code "51") (name "unconnected-(U$1-13_NC-PadP13)") (class "Default")
      (node (ref "U$1") (pin "P13") (pinfunction "13_NC_P13") (pintype "bidirectional"))
    )
    (net (code "52") (name "unconnected-(U$1-14_NC-PadP14)") (class "Default")
      (node (ref "U$1") (pin "P14") (pinfunction "14_NC_P14") (pintype "bidirectional"))
    )
    (net (code "53") (name "unconnected-(U$1-15_NC-PadP15)") (class "Default")
      (node (ref "U$1") (pin "P15") (pinfunction "15_NC_P15") (pintype "bidirectional"))
    )
    (net (code "54") (name "unconnected-(U$1-17_NC-PadP17)") (class "Default")
      (node (ref "U$1") (pin "P17") (pinfunction "17_NC_P17") (pintype "bidirectional"))
    )
    (net (code "55") (name "unconnected-(U$1-20_NC-PadP20)") (class "Default")
      (node (ref "U$1") (pin "P20") (pinfunction "20_NC_P20") (pintype "bidirectional"))
    )
    (net (code "56") (name "unconnected-(U$1-25_ANTSEL1-PadP25)") (class "Default")
      (node (ref "U$1") (pin "P25") (pinfunction "25_ANTSEL1_P25") (pintype "bidirectional"))
    )
    (net (code "57") (name "unconnected-(U$1-26_ANTSEL2-PadP26)") (class "Default")
      (node (ref "U$1") (pin "P26") (pinfunction "26_ANTSEL2_P26") (pintype "bidirectional"))
    )
    (net (code "58") (name "unconnected-(U$1-29_NC-PadP29)") (class "Default")
      (node (ref "U$1") (pin "P29") (pinfunction "29_NC_P29") (pintype "bidirectional"))
    )
    (net (code "59") (name "unconnected-(U$1-33_NC-PadP33)") (class "Default")
      (node (ref "U$1") (pin "P33") (pinfunction "33_NC_P33") (pintype "bidirectional"))
    )
    (net (code "60") (name "unconnected-(U$1-39_VDD_ANA2-PadP39)") (class "Default")
      (node (ref "U$1") (pin "P39") (pinfunction "39_VDD_ANA2_P39") (pintype "bidirectional"))
    )
    (net (code "61") (name "unconnected-(U$1-41_NC-PadP41)") (class "Default")
      (node (ref "U$1") (pin "P41") (pinfunction "41_NC_P41") (pintype "bidirectional"))
    )
    (net (code "62") (name "unconnected-(U$1-45_NC-PadP45)") (class "Default")
      (node (ref "U$1") (pin "P45") (pinfunction "45_NC_P45") (pintype "bidirectional"))
    )
    (net (code "63") (name "unconnected-(U$2-Pad1_RESERVED)") (class "Default")
      (node (ref "U$2") (pin "1_RESERVED") (pinfunction "1_RESERVED_1_RESERVED") (pintype "bidirectional"))
    )
    (net (code "64") (name "unconnected-(U$2-Pad2_SS_N)") (class "Default")
      (node (ref "U$2") (pin "2_SS_N") (pinfunction "2_SS_N_2_SS_N") (pintype "bidirectional"))
    )
    (net (code "65") (name "unconnected-(U$2-Pad4_EXTINT0)") (class "Default")
      (node (ref "U$2") (pin "4_EXTINT0") (pinfunction "4_EXTINT0_4_EXTINT0") (pintype "bidirectional"))
    )
    (net (code "66") (name "unconnected-(U$2-Pad5_USB_DM)") (class "Default")
      (node (ref "U$2") (pin "5_USB_DM") (pinfunction "5_USB_DM_5_USB_DM") (pintype "bidirectional"))
    )
    (net (code "67") (name "unconnected-(U$2-Pad6_USB_DP)") (class "Default")
      (node (ref "U$2") (pin "6_USB_DP") (pinfunction "6_USB_DP_6_USB_DP") (pintype "bidirectional"))
    )
    (net (code "68") (name "unconnected-(U$2-Pad8_RESERVED)") (class "Default")
      (node (ref "U$2") (pin "8_RESERVED") (pinfunction "8_RESERVED_8_RESERVED") (pintype "bidirectional"))
    )
    (net (code "69") (name "unconnected-(U$2-Pad9_VCC_RF)") (class "Default")
      (node (ref "U$2") (pin "9_VCC_RF") (pinfunction "9_VCC_RF_9_VCC_RF") (pintype "bidirectional"))
    )
    (net (code "70") (name "unconnected-(U$2-Pad11_RF_IN)") (class "Default")
      (node (ref "U$2") (pin "11_RF_IN") (pinfunction "11_RF_IN_11_RF_IN") (pintype "bidirectional"))
    )
    (net (code "71") (name "unconnected-(U$2-Pad14_MOSI{slash}CFG_COM0)") (class "Default")
      (node (ref "U$2") (pin "14_MOSI/CFG_COM0") (pinfunction "14_MOSI/CFG_COM0_14_MOSI/CFG_COM0") (pintype "bidirectional"))
    )
    (net (code "72") (name "unconnected-(U$2-Pad15_MISO{slash}CFG_COM1)") (class "Default")
      (node (ref "U$2") (pin "15_MISO/CFG_COM1") (pinfunction "15_MISO/CFG_COM1_15_MISO/CFG_COM1") (pintype "bidirectional"))
    )
    (net (code "73") (name "unconnected-(U$2-Pad16_CFG_CPS0{slash}SCK)") (class "Default")
      (node (ref "U$2") (pin "16_CFG_CPS0/SCK") (pinfunction "16_CFG_CPS0/SCK_16_CFG_CPS0/SCK") (pintype "bidirectional"))
    )
    (net (code "74") (name "unconnected-(U$2-Pad17_RESERVED)") (class "Default")
      (node (ref "U$2") (pin "17_RESERVED") (pinfunction "17_RESERVED_17_RESERVED") (pintype "bidirectional"))
    )
    (net (code "75") (name "unconnected-(U$2-Pad18_SDA2)") (class "Default")
      (node (ref "U$2") (pin "18_SDA2") (pinfunction "18_SDA2_18_SDA2") (pintype "bidirectional"))
    )
    (net (code "76") (name "unconnected-(U$2-Pad19_SCL2)") (class "Default")
      (node (ref "U$2") (pin "19_SCL2") (pinfunction "19_SCL2_19_SCL2") (pintype "bidirectional"))
    )
    (net (code "77") (name "unconnected-(U1-NC-Pad3)") (class "Default")
      (node (ref "U1") (pin "3") (pinfunction "NC_3") (pintype "bidirectional"))
    )
    (net (code "78") (name "unconnected-(U1-NC-Pad10)") (class "Default")
      (node (ref "U1") (pin "10") (pinfunction "NC_10") (pintype "bidirectional"))
    )
    (net (code "79") (name "unconnected-(U1-NC-Pad11)") (class "Default")
      (node (ref "U1") (pin "11") (pinfunction "NC_11") (pintype "bidirectional"))
    )
    (net (code "80") (name "unconnected-(U2-NC-Pad3)") (class "Default")
      (node (ref "U2") (pin "3") (pinfunction "NC_3") (pintype "bidirectional"))
    )
    (net (code "81") (name "unconnected-(U2-NC-Pad5)") (class "Default")
      (node (ref "U2") (pin "5") (pinfunction "NC_5") (pintype "bidirectional"))
    )
    (net (code "82") (name "unconnected-(U2-NC-Pad6)") (class "Default")
      (node (ref "U2") (pin "6") (pinfunction "NC_6") (pintype "bidirectional"))
    )
    (net (code "83") (name "unconnected-(U2-NC-Pad7)") (class "Default")
      (node (ref "U2") (pin "7") (pinfunction "NC_7") (pintype "bidirectional"))
    )
    (net (code "84") (name "unconnected-(U2-NC-Pad14)") (class "Default")
      (node (ref "U2") (pin "14") (pinfunction "NC_14") (pintype "bidirectional"))
    )
    (net (code "85") (name "unconnected-(U4-NC{slash}DOUT-Pad6)") (class "Default")
      (node (ref "U4") (pin "6") (pinfunction "NC/DOUT_6") (pintype "bidirectional"))
    )
  )
)
